# baxandall.net
KiCad netlist of a schematic drawn in EAGLE
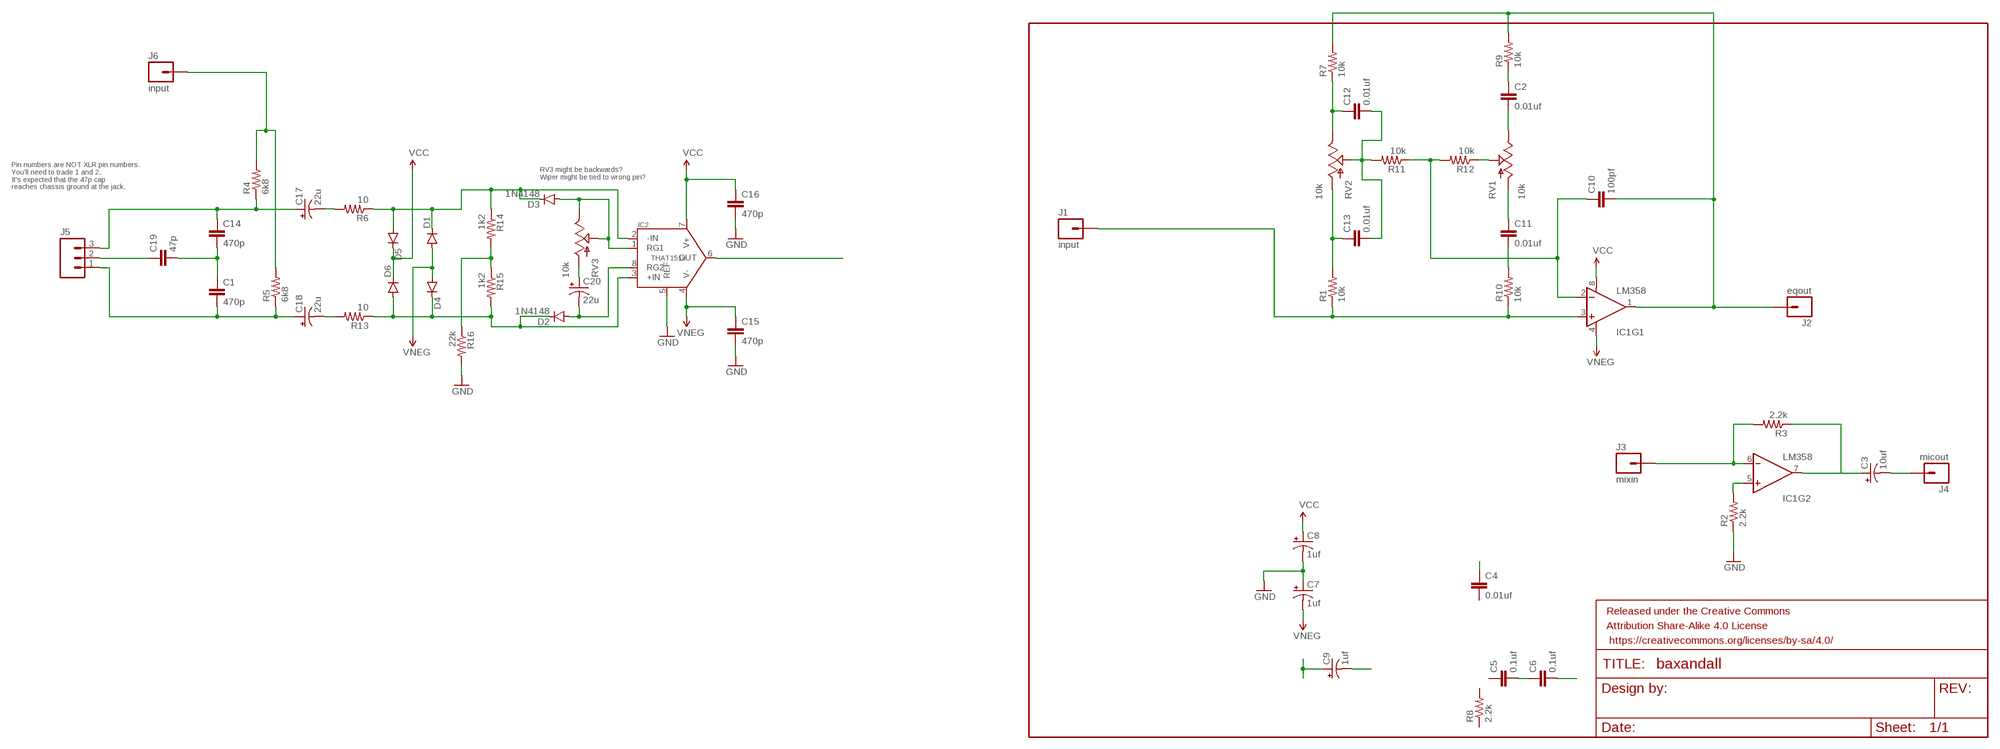
[diagram p0: schematic, sheet 1]

(export (version "E")
  (design (tool "Eeschema 10.0.6"))
  (components
    (comp (ref "C1")
      (value "470p")
      (footprint "eagle-import:CAP-PTH-SMALL")
      (libsource (lib "eagle-import") (part "CAPPTH"))
    )
    (comp (ref "C2")
      (value "0.01uf")
      (footprint "eagle-import:CAP-PTH-SMALL")
      (libsource (lib "eagle-import") (part "CAPPTH"))
    )
    (comp (ref "C3")
      (value "10uf")
      (footprint "eagle-import:CPOL-RADIAL-10UF-25V")
      (libsource (lib "eagle-import") (part "10UF-25V-20%(PTH)"))
    )
    (comp (ref "C4")
      (value "0.01uf")
      (footprint "eagle-import:CAP-PTH-SMALL")
      (libsource (lib "eagle-import") (part "CAPPTH"))
    )
    (comp (ref "C5")
      (value "0.1uf")
      (footprint "eagle-import:CAP-PTH-SMALL")
      (libsource (lib "eagle-import") (part "CAPPTH"))
    )
    (comp (ref "C6")
      (value "0.1uf")
      (footprint "eagle-import:CAP-PTH-SMALL")
      (libsource (lib "eagle-import") (part "CAPPTH"))
    )
    (comp (ref "C7")
      (value "1uf")
      (footprint "eagle-import:CPOL-RADIAL-10UF-25V")
      (libsource (lib "eagle-import") (part "CAP_POLPTH2"))
    )
    (comp (ref "C8")
      (value "1uf")
      (footprint "eagle-import:CPOL-RADIAL-10UF-25V")
      (libsource (lib "eagle-import") (part "CAP_POLPTH2"))
    )
    (comp (ref "C9")
      (value "1uf")
      (footprint "eagle-import:CPOL-RADIAL-10UF-25V")
      (libsource (lib "eagle-import") (part "CAP_POLPTH2"))
    )
    (comp (ref "C10")
      (value "100pf")
      (footprint "eagle-import:CAP-PTH-SMALL")
      (libsource (lib "eagle-import") (part "CAPPTH"))
    )
    (comp (ref "C11")
      (value "0.01uf")
      (footprint "eagle-import:CAP-PTH-SMALL")
      (libsource (lib "eagle-import") (part "CAPPTH"))
    )
    (comp (ref "C12")
      (value "0.01uf")
      (footprint "eagle-import:CAP-PTH-SMALL")
      (libsource (lib "eagle-import") (part "CAPPTH"))
    )
    (comp (ref "C13")
      (value "0.01uf")
      (footprint "eagle-import:CAP-PTH-SMALL")
      (libsource (lib "eagle-import") (part "CAPPTH"))
    )
    (comp (ref "C14")
      (value "470p")
      (footprint "eagle-import:CAP-PTH-SMALL")
      (libsource (lib "eagle-import") (part "CAPPTH"))
    )
    (comp (ref "C15")
      (value "470p")
      (footprint "eagle-import:CAP-PTH-SMALL")
      (libsource (lib "eagle-import") (part "CAPPTH"))
    )
    (comp (ref "C16")
      (value "470p")
      (footprint "eagle-import:CAP-PTH-SMALL")
      (libsource (lib "eagle-import") (part "CAPPTH"))
    )
    (comp (ref "C17")
      (value "22u")
      (footprint "eagle-import:CPOL-RADIAL-100UF-25V")
      (libsource (lib "eagle-import") (part "100UF-25V-20%(PTH)"))
    )
    (comp (ref "C18")
      (value "22u")
      (footprint "eagle-import:CPOL-RADIAL-100UF-25V")
      (libsource (lib "eagle-import") (part "100UF-25V-20%(PTH)"))
    )
    (comp (ref "C19")
      (value "47p")
      (footprint "eagle-import:CAP-PTH-SMALL")
      (libsource (lib "eagle-import") (part "CAPPTH"))
    )
    (comp (ref "C20")
      (value "22u")
      (footprint "eagle-import:CPOL-RADIAL-100UF-25V")
      (libsource (lib "eagle-import") (part "100UF-25V-20%(PTH)"))
    )
    (comp (ref "D1")
      (value "DIODEKIT2")
      (footprint "eagle-import:DIODE-1N4001-KIT")
      (libsource (lib "eagle-import") (part "DIODEKIT2"))
    )
    (comp (ref "D2")
      (value "1N4148")
      (footprint "eagle-import:DIODE-1N4148")
      (libsource (lib "eagle-import") (part "DIODE1N4148"))
    )
    (comp (ref "D3")
      (value "1N4148")
      (footprint "eagle-import:DIODE-1N4148")
      (libsource (lib "eagle-import") (part "DIODE1N4148"))
    )
    (comp (ref "D4")
      (value "DIODEKIT2")
      (footprint "eagle-import:DIODE-1N4001-KIT")
      (libsource (lib "eagle-import") (part "DIODEKIT2"))
    )
    (comp (ref "D5")
      (value "DIODEKIT2")
      (footprint "eagle-import:DIODE-1N4001-KIT")
      (libsource (lib "eagle-import") (part "DIODEKIT2"))
    )
    (comp (ref "D6")
      (value "DIODEKIT2")
      (footprint "eagle-import:DIODE-1N4001-KIT")
      (libsource (lib "eagle-import") (part "DIODEKIT2"))
    )
    (comp (ref "FRAME1")
      (value "FRAME-LETTER")
      (footprint "eagle-import:CREATIVE_COMMONS")
      (libsource (lib "eagle-import") (part "FRAME-LETTER"))
    )
    (comp (ref "IC1")
      (value "LM358")
      (footprint "eagle-import:DIP08")
      (libsource (lib "eagle-import") (part "LM358"))
    )
    (comp (ref "IC2")
      (value "THAT151x")
      (footprint "eagle-import:DIP08-KIT")
      (libsource (lib "eagle-import") (part "THAT151X"))
    )
    (comp (ref "J1")
      (value "input")
      (footprint "eagle-import:1X01NS-KIT")
      (libsource (lib "eagle-import") (part "M01NOSILK-KIT"))
    )
    (comp (ref "J2")
      (value "eqout")
      (footprint "eagle-import:1X01NS-KIT")
      (libsource (lib "eagle-import") (part "M01NOSILK-KIT"))
    )
    (comp (ref "J3")
      (value "mixin")
      (footprint "eagle-import:1X01NS-KIT")
      (libsource (lib "eagle-import") (part "M01NOSILK-KIT"))
    )
    (comp (ref "J4")
      (value "micout")
      (footprint "eagle-import:1X01NS-KIT")
      (libsource (lib "eagle-import") (part "M01NOSILK-KIT"))
    )
    (comp (ref "J5")
      (value "M031X03_NO_SILK")
      (footprint "eagle-import:1X03_NO_SILK")
      (libsource (lib "eagle-import") (part "M031X03_NO_SILK"))
    )
    (comp (ref "J6")
      (value "input")
      (footprint "eagle-import:1X01NS-KIT")
      (libsource (lib "eagle-import") (part "M01NOSILK-KIT"))
    )
    (comp (ref "R1")
      (value "10k")
      (footprint "eagle-import:AXIAL-0.3")
      (libsource (lib "eagle-import") (part "10KOHM-1/4W-1%(PTH)HORIZ"))
    )
    (comp (ref "R2")
      (value "2.2k")
      (footprint "eagle-import:AXIAL-0.3")
      (libsource (lib "eagle-import") (part "RESISTORAXIAL-0.3"))
    )
    (comp (ref "R3")
      (value "2.2k")
      (footprint "eagle-import:AXIAL-0.3")
      (libsource (lib "eagle-import") (part "RESISTORAXIAL-0.3"))
    )
    (comp (ref "R4")
      (value "6k8")
      (footprint "eagle-import:AXIAL-0.3")
      (libsource (lib "eagle-import") (part "10KOHM-1/4W-1%(PTH)HORIZ"))
    )
    (comp (ref "R5")
      (value "6k8")
      (footprint "eagle-import:AXIAL-0.3")
      (libsource (lib "eagle-import") (part "10KOHM-1/4W-1%(PTH)HORIZ"))
    )
    (comp (ref "R6")
      (value "10")
      (footprint "eagle-import:AXIAL-0.3")
      (libsource (lib "eagle-import") (part "10KOHM-1/4W-1%(PTH)HORIZ"))
    )
    (comp (ref "R7")
      (value "10k")
      (footprint "eagle-import:AXIAL-0.3")
      (libsource (lib "eagle-import") (part "10KOHM-1/4W-1%(PTH)HORIZ"))
    )
    (comp (ref "R8")
      (value "2.2k")
      (footprint "eagle-import:AXIAL-0.3")
      (libsource (lib "eagle-import") (part "RESISTORAXIAL-0.3"))
    )
    (comp (ref "R9")
      (value "10k")
      (footprint "eagle-import:AXIAL-0.3")
      (libsource (lib "eagle-import") (part "10KOHM-1/4W-1%(PTH)HORIZ"))
    )
    (comp (ref "R10")
      (value "10k")
      (footprint "eagle-import:AXIAL-0.3")
      (libsource (lib "eagle-import") (part "10KOHM-1/4W-1%(PTH)HORIZ"))
    )
    (comp (ref "R11")
      (value "10k")
      (footprint "eagle-import:AXIAL-0.3")
      (libsource (lib "eagle-import") (part "10KOHM-1/4W-1%(PTH)HORIZ"))
    )
    (comp (ref "R12")
      (value "10k")
      (footprint "eagle-import:AXIAL-0.3")
      (libsource (lib "eagle-import") (part "10KOHM-1/4W-1%(PTH)HORIZ"))
    )
    (comp (ref "R13")
      (value "10")
      (footprint "eagle-import:AXIAL-0.3")
      (libsource (lib "eagle-import") (part "10KOHM-1/4W-1%(PTH)HORIZ"))
    )
    (comp (ref "R14")
      (value "1k2")
      (footprint "eagle-import:AXIAL-0.3")
      (libsource (lib "eagle-import") (part "10KOHM-1/4W-1%(PTH)HORIZ"))
    )
    (comp (ref "R15")
      (value "1k2")
      (footprint "eagle-import:AXIAL-0.3")
      (libsource (lib "eagle-import") (part "10KOHM-1/4W-1%(PTH)HORIZ"))
    )
    (comp (ref "R16")
      (value "22k")
      (footprint "eagle-import:AXIAL-0.3")
      (libsource (lib "eagle-import") (part "10KOHM-1/4W-1%(PTH)HORIZ"))
    )
    (comp (ref "RV1")
      (value "10k")
      (footprint "eagle-import:POT_ALPHA_RV16AF-20")
      (libsource (lib "eagle-import") (part "POT-RV16AF-20"))
    )
    (comp (ref "RV2")
      (value "10k")
      (footprint "eagle-import:POT_ALPHA_RV16AF-20")
      (libsource (lib "eagle-import") (part "POT-RV16AF-20"))
    )
    (comp (ref "RV3")
      (value "10k")
      (footprint "eagle-import:POT_ALPHA_RV16AF-20")
      (libsource (lib "eagle-import") (part "POT-RV16AF-20"))
    )
  )
  (nets
    (net (code "1") (name "GND") (class "Default")
      (node (ref "C15") (pin "2") (pinfunction "2_2") (pintype "passive"))
      (node (ref "C16") (pin "2") (pinfunction "2_2") (pintype "passive"))
      (node (ref "C7") (pin "1") (pinfunction "+_1") (pintype "passive"))
      (node (ref "C8") (pin "2") (pinfunction "-_2") (pintype "passive"))
      (node (ref "IC2") (pin "5") (pinfunction "REF_5") (pintype "bidirectional"))
      (node (ref "R16") (pin "P$2") (pinfunction "2_P$2") (pintype "passive"))
      (node (ref "R2") (pin "P$1") (pinfunction "1_P$1") (pintype "passive"))
    )
    (net (code "2") (name "Net-(C1-Pad1)") (class "Default")
      (node (ref "C1") (pin "1") (pinfunction "1_1") (pintype "passive"))
      (node (ref "C14") (pin "2") (pinfunction "2_2") (pintype "passive"))
      (node (ref "C19") (pin "2") (pinfunction "2_2") (pintype "passive"))
    )
    (net (code "3") (name "Net-(C3-+)") (class "Default")
      (node (ref "C3") (pin "1") (pinfunction "+_1") (pintype "passive"))
      (node (ref "IC1") (pin "7") (pinfunction "OUT_7") (pintype "output"))
      (node (ref "R3") (pin "P$1") (pinfunction "1_P$1") (pintype "passive"))
    )
    (net (code "4") (name "Net-(C3--)") (class "Default")
      (node (ref "C3") (pin "2") (pinfunction "-_2") (pintype "passive"))
      (node (ref "J4") (pin "1") (pinfunction "1_1") (pintype "passive"))
    )
    (net (code "5") (name "Net-(C5-Pad2)") (class "Default")
      (node (ref "C5") (pin "2") (pinfunction "2_2") (pintype "passive"))
      (node (ref "C6") (pin "1") (pinfunction "1_1") (pintype "passive"))
    )
    (net (code "6") (name "Net-(C17-+)") (class "Default")
      (node (ref "C14") (pin "1") (pinfunction "1_1") (pintype "passive"))
      (node (ref "C17") (pin "1") (pinfunction "+_1") (pintype "passive"))
      (node (ref "J5") (pin "3") (pinfunction "3_3") (pintype "passive"))
      (node (ref "R4") (pin "P$1") (pinfunction "1_P$1") (pintype "passive"))
    )
    (net (code "7") (name "Net-(C17--)") (class "Default")
      (node (ref "C17") (pin "2") (pinfunction "-_2") (pintype "passive"))
      (node (ref "R6") (pin "P$2") (pinfunction "2_P$2") (pintype "passive"))
    )
    (net (code "8") (name "Net-(C18-+)") (class "Default")
      (node (ref "C1") (pin "2") (pinfunction "2_2") (pintype "passive"))
      (node (ref "C18") (pin "1") (pinfunction "+_1") (pintype "passive"))
      (node (ref "J5") (pin "1") (pinfunction "1_1") (pintype "passive"))
      (node (ref "R5") (pin "P$1") (pinfunction "1_P$1") (pintype "passive"))
    )
    (net (code "9") (name "Net-(C18--)") (class "Default")
      (node (ref "C18") (pin "2") (pinfunction "-_2") (pintype "passive"))
      (node (ref "R13") (pin "P$2") (pinfunction "2_P$2") (pintype "passive"))
    )
    (net (code "10") (name "Net-(C19-Pad1)") (class "Default")
      (node (ref "C19") (pin "1") (pinfunction "1_1") (pintype "passive"))
      (node (ref "J5") (pin "2") (pinfunction "2_2") (pintype "passive"))
    )
    (net (code "11") (name "Net-(C20-+)") (class "Default")
      (node (ref "C20") (pin "1") (pinfunction "+_1") (pintype "passive"))
      (node (ref "RV3") (pin "1") (pinfunction "A_1") (pintype "passive"))
    )
    (net (code "12") (name "Net-(C20--)") (class "Default")
      (node (ref "C20") (pin "2") (pinfunction "-_2") (pintype "passive"))
      (node (ref "D2") (pin "A") (pinfunction "A_A") (pintype "passive"))
      (node (ref "IC2") (pin "8") (pinfunction "RG2_8") (pintype "bidirectional"))
    )
    (net (code "13") (name "Net-(IC1A-+IN)") (class "Default")
      (node (ref "IC1") (pin "3") (pinfunction "+IN_3") (pintype "input"))
      (node (ref "J1") (pin "1") (pinfunction "1_1") (pintype "passive"))
      (node (ref "R1") (pin "P$1") (pinfunction "1_P$1") (pintype "passive"))
      (node (ref "R10") (pin "P$1") (pinfunction "1_P$1") (pintype "passive"))
    )
    (net (code "14") (name "Net-(IC1A--IN)") (class "Default")
      (node (ref "C10") (pin "1") (pinfunction "1_1") (pintype "passive"))
      (node (ref "IC1") (pin "2") (pinfunction "-IN_2") (pintype "input"))
      (node (ref "R11") (pin "P$1") (pinfunction "1_P$1") (pintype "passive"))
      (node (ref "R12") (pin "P$2") (pinfunction "2_P$2") (pintype "passive"))
    )
    (net (code "15") (name "Net-(IC1A-OUT)") (class "Default")
      (node (ref "C10") (pin "2") (pinfunction "2_2") (pintype "passive"))
      (node (ref "IC1") (pin "1") (pinfunction "OUT_1") (pintype "output"))
      (node (ref "J2") (pin "1") (pinfunction "1_1") (pintype "passive"))
      (node (ref "R7") (pin "P$2") (pinfunction "2_P$2") (pintype "passive"))
      (node (ref "R9") (pin "P$2") (pinfunction "2_P$2") (pintype "passive"))
    )
    (net (code "16") (name "Net-(IC1B-+IN)") (class "Default")
      (node (ref "IC1") (pin "5") (pinfunction "+IN_5") (pintype "input"))
      (node (ref "R2") (pin "P$2") (pinfunction "2_P$2") (pintype "passive"))
    )
    (net (code "17") (name "Net-(IC1B--IN)") (class "Default")
      (node (ref "IC1") (pin "6") (pinfunction "-IN_6") (pintype "input"))
      (node (ref "J3") (pin "1") (pinfunction "1_1") (pintype "passive"))
      (node (ref "R3") (pin "P$2") (pinfunction "2_P$2") (pintype "passive"))
    )
    (net (code "18") (name "Net-(IC2-+IN)") (class "Default")
      (node (ref "D2") (pin "C") (pinfunction "C_C") (pintype "passive"))
      (node (ref "D4") (pin "C") (pinfunction "C_C") (pintype "passive"))
      (node (ref "D6") (pin "A") (pinfunction "A_A") (pintype "passive"))
      (node (ref "IC2") (pin "3") (pinfunction "+IN_3") (pintype "bidirectional"))
      (node (ref "R13") (pin "P$1") (pinfunction "1_P$1") (pintype "passive"))
      (node (ref "R15") (pin "P$2") (pinfunction "2_P$2") (pintype "passive"))
    )
    (net (code "19") (name "Net-(IC2--IN)") (class "Default")
      (node (ref "D1") (pin "C") (pinfunction "C_C") (pintype "passive"))
      (node (ref "D3") (pin "C") (pinfunction "C_C") (pintype "passive"))
      (node (ref "D5") (pin "A") (pinfunction "A_A") (pintype "passive"))
      (node (ref "IC2") (pin "2") (pinfunction "-IN_2") (pintype "bidirectional"))
      (node (ref "R14") (pin "P$1") (pinfunction "1_P$1") (pintype "passive"))
      (node (ref "R6") (pin "P$1") (pinfunction "1_P$1") (pintype "passive"))
    )
    (net (code "20") (name "Net-(IC2-RG1)") (class "Default")
      (node (ref "D3") (pin "A") (pinfunction "A_A") (pintype "passive"))
      (node (ref "IC2") (pin "1") (pinfunction "RG1_1") (pintype "bidirectional"))
      (node (ref "RV3") (pin "2") (pinfunction "S_2") (pintype "passive"))
      (node (ref "RV3") (pin "3") (pinfunction "E_3") (pintype "passive"))
    )
    (net (code "21") (name "Net-(R1-2)") (class "Default")
      (node (ref "C13") (pin "1") (pinfunction "1_1") (pintype "passive"))
      (node (ref "R1") (pin "P$2") (pinfunction "2_P$2") (pintype "passive"))
      (node (ref "RV2") (pin "1") (pinfunction "A_1") (pintype "passive"))
    )
    (net (code "22") (name "Net-(R4-2)") (class "Default")
      (node (ref "J6") (pin "1") (pinfunction "1_1") (pintype "passive"))
      (node (ref "R4") (pin "P$2") (pinfunction "2_P$2") (pintype "passive"))
      (node (ref "R5") (pin "P$2") (pinfunction "2_P$2") (pintype "passive"))
    )
    (net (code "23") (name "Net-(R7-1)") (class "Default")
      (node (ref "C12") (pin "1") (pinfunction "1_1") (pintype "passive"))
      (node (ref "R7") (pin "P$1") (pinfunction "1_P$1") (pintype "passive"))
      (node (ref "RV2") (pin "3") (pinfunction "E_3") (pintype "passive"))
    )
    (net (code "24") (name "Net-(R9-1)") (class "Default")
      (node (ref "C2") (pin "1") (pinfunction "1_1") (pintype "passive"))
      (node (ref "R9") (pin "P$1") (pinfunction "1_P$1") (pintype "passive"))
    )
    (net (code "25") (name "Net-(R10-2)") (class "Default")
      (node (ref "C11") (pin "2") (pinfunction "2_2") (pintype "passive"))
      (node (ref "R10") (pin "P$2") (pinfunction "2_P$2") (pintype "passive"))
    )
    (net (code "26") (name "Net-(R11-2)") (class "Default")
      (node (ref "C12") (pin "2") (pinfunction "2_2") (pintype "passive"))
      (node (ref "C13") (pin "2") (pinfunction "2_2") (pintype "passive"))
      (node (ref "R11") (pin "P$2") (pinfunction "2_P$2") (pintype "passive"))
      (node (ref "RV2") (pin "2") (pinfunction "S_2") (pintype "passive"))
    )
    (net (code "27") (name "Net-(R12-1)") (class "Default")
      (node (ref "R12") (pin "P$1") (pinfunction "1_P$1") (pintype "passive"))
      (node (ref "RV1") (pin "2") (pinfunction "S_2") (pintype "passive"))
    )
    (net (code "28") (name "Net-(R14-2)") (class "Default")
      (node (ref "R14") (pin "P$2") (pinfunction "2_P$2") (pintype "passive"))
      (node (ref "R15") (pin "P$1") (pinfunction "1_P$1") (pintype "passive"))
      (node (ref "R16") (pin "P$1") (pinfunction "1_P$1") (pintype "passive"))
    )
    (net (code "29") (name "Net-(RV1-A)") (class "Default")
      (node (ref "C11") (pin "1") (pinfunction "1_1") (pintype "passive"))
      (node (ref "RV1") (pin "1") (pinfunction "A_1") (pintype "passive"))
    )
    (net (code "30") (name "Net-(RV1-E)") (class "Default")
      (node (ref "C2") (pin "2") (pinfunction "2_2") (pintype "passive"))
      (node (ref "RV1") (pin "3") (pinfunction "E_3") (pintype "passive"))
    )
    (net (code "31") (name "VCC") (class "Default")
      (node (ref "C16") (pin "1") (pinfunction "1_1") (pintype "passive"))
      (node (ref "C8") (pin "1") (pinfunction "+_1") (pintype "passive"))
      (node (ref "D5") (pin "C") (pinfunction "C_C") (pintype "passive"))
      (node (ref "D6") (pin "C") (pinfunction "C_C") (pintype "passive"))
      (node (ref "IC1") (pin "8") (pinfunction "V+_8") (pintype "power_in"))
      (node (ref "IC2") (pin "7") (pinfunction "V+_7") (pintype "bidirectional"))
    )
    (net (code "32") (name "VNEG") (class "Default")
      (node (ref "C15") (pin "1") (pinfunction "1_1") (pintype "passive"))
      (node (ref "C7") (pin "2") (pinfunction "-_2") (pintype "passive"))
      (node (ref "D1") (pin "A") (pinfunction "A_A") (pintype "passive"))
      (node (ref "D4") (pin "A") (pinfunction "A_A") (pintype "passive"))
      (node (ref "IC1") (pin "4") (pinfunction "V-_4") (pintype "power_in"))
      (node (ref "IC2") (pin "4") (pinfunction "V-_4") (pintype "bidirectional"))
    )
    (net (code "33") (name "unconnected-(C4-Pad1)") (class "Default")
      (node (ref "C4") (pin "1") (pinfunction "1_1") (pintype "passive"))
    )
    (net (code "34") (name "unconnected-(C4-Pad2)") (class "Default")
      (node (ref "C4") (pin "2") (pinfunction "2_2") (pintype "passive"))
    )
    (net (code "35") (name "unconnected-(C5-Pad1)") (class "Default")
      (node (ref "C5") (pin "1") (pinfunction "1_1") (pintype "passive"))
    )
    (net (code "36") (name "unconnected-(C6-Pad2)") (class "Default")
      (node (ref "C6") (pin "2") (pinfunction "2_2") (pintype "passive"))
    )
    (net (code "37") (name "unconnected-(C9-+-Pad1)") (class "Default")
      (node (ref "C9") (pin "1") (pinfunction "+_1") (pintype "passive"))
    )
    (net (code "38") (name "unconnected-(C9---Pad2)") (class "Default")
      (node (ref "C9") (pin "2") (pinfunction "-_2") (pintype "passive"))
    )
    (net (code "39") (name "unconnected-(IC2-OUT-Pad6)") (class "Default")
      (node (ref "IC2") (pin "6") (pinfunction "OUT_6") (pintype "bidirectional"))
    )
    (net (code "40") (name "unconnected-(R8-1-PadP$1)") (class "Default")
      (node (ref "R8") (pin "P$1") (pinfunction "1_P$1") (pintype "passive"))
    )
    (net (code "41") (name "unconnected-(R8-2-PadP$2)") (class "Default")
      (node (ref "R8") (pin "P$2") (pinfunction "2_P$2") (pintype "passive"))
    )
  )
)
